# BusBreakout_I2C_Mini.net
KiCad netlist of a schematic drawn in EAGLE
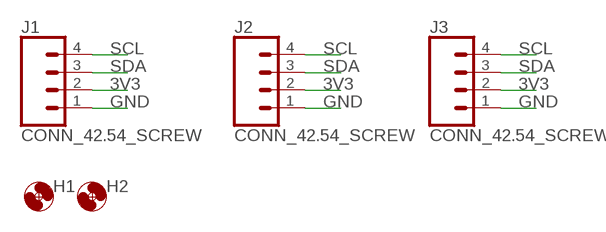
[diagram p0: schematic, sheet 1]

(export (version "E")
  (design (tool "Eeschema 10.0.6"))
  (components
    (comp (ref "H1")
      (value "MOUNTING_HOLE4_NP")
      (footprint "eagle-import:4_40")
      (fields (field (name "MPN") "DNP"))
      (libsource (lib "eagle-import") (part "MOUNTING_HOLE4_NP"))
    )
    (comp (ref "H2")
      (value "MOUNTING_HOLE4_NP")
      (footprint "eagle-import:4_40")
      (fields (field (name "MPN") "DNP"))
      (libsource (lib "eagle-import") (part "MOUNTING_HOLE4_NP"))
    )
    (comp (ref "J1")
      (value "CONN_42.54_SCREW")
      (footprint "eagle-import:1X04_SCREW")
      (fields (field (name "MF") "On Shore") (field (name "MPN") "OSTVN04A150"))
      (libsource (lib "eagle-import") (part "CONN_42.54_SCREW"))
    )
    (comp (ref "J2")
      (value "CONN_42.54_SCREW")
      (footprint "eagle-import:1X04_SCREW")
      (fields (field (name "MF") "On Shore") (field (name "MPN") "OSTVN04A150"))
      (libsource (lib "eagle-import") (part "CONN_42.54_SCREW"))
    )
    (comp (ref "J3")
      (value "CONN_42.54_SCREW")
      (footprint "eagle-import:1X04_SCREW")
      (fields (field (name "MF") "On Shore") (field (name "MPN") "OSTVN04A150"))
      (libsource (lib "eagle-import") (part "CONN_42.54_SCREW"))
    )
  )
  (nets
    (net (code "1") (name "/3V3") (class "Default")
      (node (ref "J1") (pin "2") (pinfunction "2_2") (pintype "passive"))
      (node (ref "J2") (pin "2") (pinfunction "2_2") (pintype "passive"))
      (node (ref "J3") (pin "2") (pinfunction "2_2") (pintype "passive"))
    )
    (net (code "2") (name "/GND") (class "Default")
      (node (ref "J1") (pin "1") (pinfunction "1_1") (pintype "passive"))
      (node (ref "J2") (pin "1") (pinfunction "1_1") (pintype "passive"))
      (node (ref "J3") (pin "1") (pinfunction "1_1") (pintype "passive"))
    )
    (net (code "3") (name "/SCL") (class "Default")
      (node (ref "J1") (pin "4") (pinfunction "4_4") (pintype "passive"))
      (node (ref "J2") (pin "4") (pinfunction "4_4") (pintype "passive"))
      (node (ref "J3") (pin "4") (pinfunction "4_4") (pintype "passive"))
    )
    (net (code "4") (name "/SDA") (class "Default")
      (node (ref "J1") (pin "3") (pinfunction "3_3") (pintype "passive"))
      (node (ref "J2") (pin "3") (pinfunction "3_3") (pintype "passive"))
      (node (ref "J3") (pin "3") (pinfunction "3_3") (pintype "passive"))
    )
  )
)
